# cpx-synth1.net
KiCad netlist of a schematic drawn in EAGLE
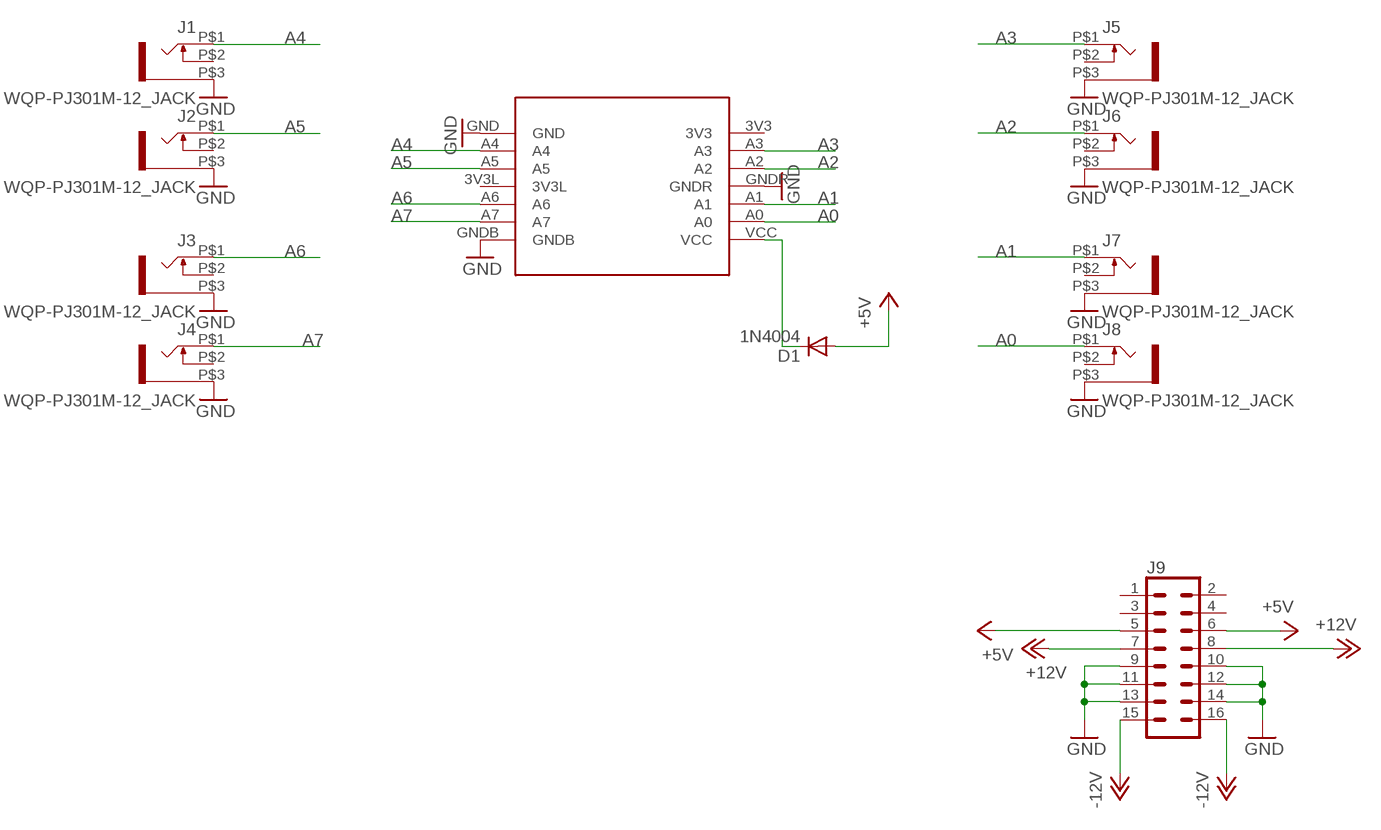
[diagram p0: schematic, sheet 1]

(export (version "E")
  (design (tool "Eeschema 10.0.6"))
  (components
    (comp (ref "D1")
      (value "1N4004")
      (footprint "eagle-import:DO41-10")
      (libsource (lib "eagle-import") (part "1N4004"))
    )
    (comp (ref "J1")
      (value "WQP-PJ301M-12_JACK")
      (footprint "eagle-import:WQP-PJ301M-12_JACK")
      (libsource (lib "eagle-import") (part "WQP-PJ301M-12_JACK"))
    )
    (comp (ref "J2")
      (value "WQP-PJ301M-12_JACK")
      (footprint "eagle-import:WQP-PJ301M-12_JACK")
      (libsource (lib "eagle-import") (part "WQP-PJ301M-12_JACK"))
    )
    (comp (ref "J3")
      (value "WQP-PJ301M-12_JACK")
      (footprint "eagle-import:WQP-PJ301M-12_JACK")
      (libsource (lib "eagle-import") (part "WQP-PJ301M-12_JACK"))
    )
    (comp (ref "J4")
      (value "WQP-PJ301M-12_JACK")
      (footprint "eagle-import:WQP-PJ301M-12_JACK")
      (libsource (lib "eagle-import") (part "WQP-PJ301M-12_JACK"))
    )
    (comp (ref "J5")
      (value "WQP-PJ301M-12_JACK")
      (footprint "eagle-import:WQP-PJ301M-12_JACK")
      (libsource (lib "eagle-import") (part "WQP-PJ301M-12_JACK"))
    )
    (comp (ref "J6")
      (value "WQP-PJ301M-12_JACK")
      (footprint "eagle-import:WQP-PJ301M-12_JACK")
      (libsource (lib "eagle-import") (part "WQP-PJ301M-12_JACK"))
    )
    (comp (ref "J7")
      (value "WQP-PJ301M-12_JACK")
      (footprint "eagle-import:WQP-PJ301M-12_JACK")
      (libsource (lib "eagle-import") (part "WQP-PJ301M-12_JACK"))
    )
    (comp (ref "J8")
      (value "WQP-PJ301M-12_JACK")
      (footprint "eagle-import:WQP-PJ301M-12_JACK")
      (libsource (lib "eagle-import") (part "WQP-PJ301M-12_JACK"))
    )
    (comp (ref "J9")
      (value "CONN_08X2")
      (footprint "eagle-import:2X8")
      (libsource (lib "eagle-import") (part "CONN_08X2"))
    )
    (comp (ref "U1")
      (value "CIRCUITPLAYGROUNDEXPRESS")
      (footprint "eagle-import:CIRCUITPLAYGROUNDEXPRESS")
      (libsource (lib "eagle-import") (part "CIRCUITPLAYGROUNDEXPRESS"))
    )
  )
  (nets
    (net (code "1") (name "+5V") (class "Default")
      (node (ref "D1") (pin "A") (pinfunction "A_A") (pintype "passive"))
      (node (ref "J9") (pin "5") (pinfunction "5_5") (pintype "passive"))
      (node (ref "J9") (pin "6") (pinfunction "6_6") (pintype "passive"))
    )
    (net (code "2") (name "+12V") (class "Default")
      (node (ref "J9") (pin "7") (pinfunction "7_7") (pintype "passive"))
      (node (ref "J9") (pin "8") (pinfunction "8_8") (pintype "passive"))
    )
    (net (code "3") (name "-12V") (class "Default")
      (node (ref "J9") (pin "15") (pinfunction "15_15") (pintype "passive"))
      (node (ref "J9") (pin "16") (pinfunction "16_16") (pintype "passive"))
    )
    (net (code "4") (name "/A0") (class "Default")
      (node (ref "J8") (pin "P$1") (pinfunction "2_P$1") (pintype "passive"))
      (node (ref "U1") (pin "A0") (pinfunction "A0_A0") (pintype "bidirectional"))
    )
    (net (code "5") (name "/A1") (class "Default")
      (node (ref "J7") (pin "P$1") (pinfunction "2_P$1") (pintype "passive"))
      (node (ref "U1") (pin "A1") (pinfunction "A1_A1") (pintype "bidirectional"))
    )
    (net (code "6") (name "/A2") (class "Default")
      (node (ref "J6") (pin "P$1") (pinfunction "2_P$1") (pintype "passive"))
      (node (ref "U1") (pin "A2") (pinfunction "A2_A2") (pintype "bidirectional"))
    )
    (net (code "7") (name "/A3") (class "Default")
      (node (ref "J5") (pin "P$1") (pinfunction "2_P$1") (pintype "passive"))
      (node (ref "U1") (pin "A3") (pinfunction "A3_A3") (pintype "bidirectional"))
    )
    (net (code "8") (name "/A4") (class "Default")
      (node (ref "J1") (pin "P$1") (pinfunction "2_P$1") (pintype "passive"))
      (node (ref "U1") (pin "A4") (pinfunction "A4_A4") (pintype "bidirectional"))
    )
    (net (code "9") (name "/A5") (class "Default")
      (node (ref "J2") (pin "P$1") (pinfunction "2_P$1") (pintype "passive"))
      (node (ref "U1") (pin "A5") (pinfunction "A5_A5") (pintype "bidirectional"))
    )
    (net (code "10") (name "/A6") (class "Default")
      (node (ref "J3") (pin "P$1") (pinfunction "2_P$1") (pintype "passive"))
      (node (ref "U1") (pin "A6") (pinfunction "A6_A6") (pintype "bidirectional"))
    )
    (net (code "11") (name "/A7") (class "Default")
      (node (ref "J4") (pin "P$1") (pinfunction "2_P$1") (pintype "passive"))
      (node (ref "U1") (pin "A7") (pinfunction "A7_A7") (pintype "bidirectional"))
    )
    (net (code "12") (name "GND") (class "Default")
      (node (ref "J1") (pin "P$3") (pinfunction "1_P$3") (pintype "passive"))
      (node (ref "J2") (pin "P$3") (pinfunction "1_P$3") (pintype "passive"))
      (node (ref "J3") (pin "P$3") (pinfunction "1_P$3") (pintype "passive"))
      (node (ref "J4") (pin "P$3") (pinfunction "1_P$3") (pintype "passive"))
      (node (ref "J5") (pin "P$3") (pinfunction "1_P$3") (pintype "passive"))
      (node (ref "J6") (pin "P$3") (pinfunction "1_P$3") (pintype "passive"))
      (node (ref "J7") (pin "P$3") (pinfunction "1_P$3") (pintype "passive"))
      (node (ref "J8") (pin "P$3") (pinfunction "1_P$3") (pintype "passive"))
      (node (ref "J9") (pin "10") (pinfunction "10_10") (pintype "passive"))
      (node (ref "J9") (pin "11") (pinfunction "11_11") (pintype "passive"))
      (node (ref "J9") (pin "12") (pinfunction "12_12") (pintype "passive"))
      (node (ref "J9") (pin "13") (pinfunction "13_13") (pintype "passive"))
      (node (ref "J9") (pin "14") (pinfunction "14_14") (pintype "passive"))
      (node (ref "J9") (pin "9") (pinfunction "9_9") (pintype "passive"))
      (node (ref "U1") (pin "GND") (pinfunction "GND_GND") (pintype "bidirectional"))
      (node (ref "U1") (pin "GNDB") (pinfunction "GNDB_GNDB") (pintype "bidirectional"))
      (node (ref "U1") (pin "GNDR") (pinfunction "GNDR_GNDR") (pintype "bidirectional"))
    )
    (net (code "13") (name "Net-(D1-PadC)") (class "Default")
      (node (ref "D1") (pin "C") (pinfunction "C_C") (pintype "passive"))
      (node (ref "U1") (pin "VCC") (pinfunction "VCC_VCC") (pintype "bidirectional"))
    )
    (net (code "14") (name "unconnected-(J1-3-PadP$2)") (class "Default")
      (node (ref "J1") (pin "P$2") (pinfunction "3_P$2") (pintype "passive"))
    )
    (net (code "15") (name "unconnected-(J2-3-PadP$2)") (class "Default")
      (node (ref "J2") (pin "P$2") (pinfunction "3_P$2") (pintype "passive"))
    )
    (net (code "16") (name "unconnected-(J3-3-PadP$2)") (class "Default")
      (node (ref "J3") (pin "P$2") (pinfunction "3_P$2") (pintype "passive"))
    )
    (net (code "17") (name "unconnected-(J4-3-PadP$2)") (class "Default")
      (node (ref "J4") (pin "P$2") (pinfunction "3_P$2") (pintype "passive"))
    )
    (net (code "18") (name "unconnected-(J5-3-PadP$2)") (class "Default")
      (node (ref "J5") (pin "P$2") (pinfunction "3_P$2") (pintype "passive"))
    )
    (net (code "19") (name "unconnected-(J6-3-PadP$2)") (class "Default")
      (node (ref "J6") (pin "P$2") (pinfunction "3_P$2") (pintype "passive"))
    )
    (net (code "20") (name "unconnected-(J7-3-PadP$2)") (class "Default")
      (node (ref "J7") (pin "P$2") (pinfunction "3_P$2") (pintype "passive"))
    )
    (net (code "21") (name "unconnected-(J8-3-PadP$2)") (class "Default")
      (node (ref "J8") (pin "P$2") (pinfunction "3_P$2") (pintype "passive"))
    )
    (net (code "22") (name "unconnected-(J9-Pad1)") (class "Default")
      (node (ref "J9") (pin "1") (pinfunction "1_1") (pintype "passive"))
    )
    (net (code "23") (name "unconnected-(J9-Pad2)") (class "Default")
      (node (ref "J9") (pin "2") (pinfunction "2_2") (pintype "passive"))
    )
    (net (code "24") (name "unconnected-(J9-Pad3)") (class "Default")
      (node (ref "J9") (pin "3") (pinfunction "3_3") (pintype "passive"))
    )
    (net (code "25") (name "unconnected-(J9-Pad4)") (class "Default")
      (node (ref "J9") (pin "4") (pinfunction "4_4") (pintype "passive"))
    )
    (net (code "26") (name "unconnected-(U1-Pad3V3)") (class "Default")
      (node (ref "U1") (pin "3V3") (pinfunction "3V3_3V3") (pintype "bidirectional"))
    )
    (net (code "27") (name "unconnected-(U1-Pad3V3L)") (class "Default")
      (node (ref "U1") (pin "3V3L") (pinfunction "3V3L_3V3L") (pintype "bidirectional"))
    )
  )
)
